# ZCD.net
KiCad netlist of a schematic drawn in Altium Designer
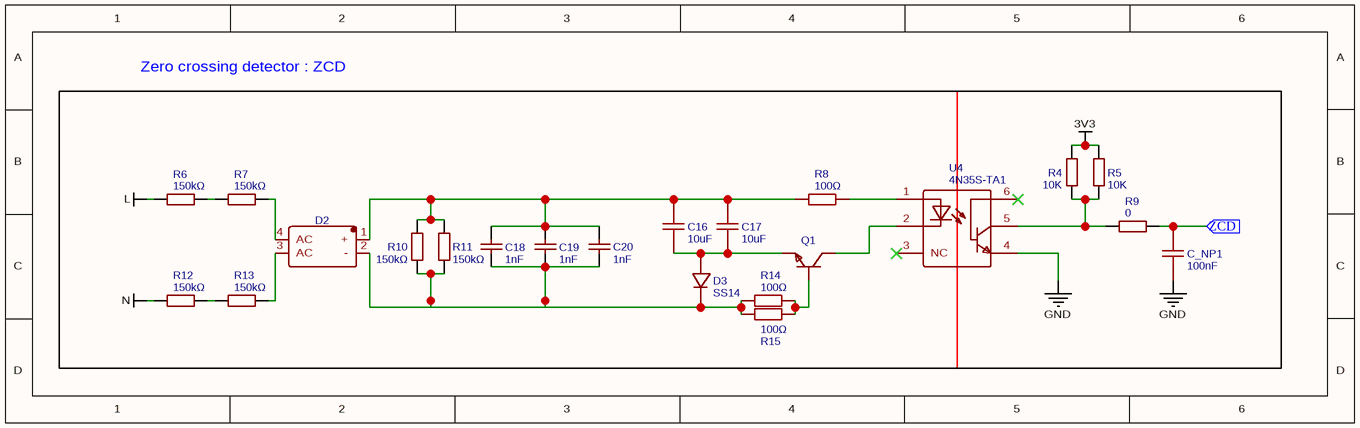
[diagram p0: ZCD.schdoc]

(export (version "E")
  (design (tool "Eeschema 10.0.6"))
  (components
    (comp (ref "C16")
      (value "10uF")
      (fields
        (field (name "BOM_MANUFACTURER PART") "0805F106M160NT")
        (field (name "BOM_SUPPLIER PART") "C90545")
      )
      (libsource (lib "altium-import") (part "root_1_10uF_"))
    )
    (comp (ref "C17")
      (value "10uF")
      (fields
        (field (name "BOM_MANUFACTURER PART") "0805F106M160NT")
        (field (name "BOM_SUPPLIER PART") "C90545")
      )
      (libsource (lib "altium-import") (part "root_1_10uF_"))
    )
    (comp (ref "C18")
      (value "1nF")
      (fields
        (field (name "BOM_MANUFACTURER PART") "CL10B102KB8NNNC")
        (field (name "BOM_SUPPLIER PART") "C1588")
      )
      (libsource (lib "altium-import") (part "root_1_1nF_"))
    )
    (comp (ref "C19")
      (value "1nF")
      (fields
        (field (name "BOM_MANUFACTURER PART") "CL10B102KB8NNNC")
        (field (name "BOM_SUPPLIER PART") "C1588")
      )
      (libsource (lib "altium-import") (part "root_1_1nF_"))
    )
    (comp (ref "C20")
      (value "1nF")
      (fields
        (field (name "BOM_MANUFACTURER PART") "CL10B102KB8NNNC")
        (field (name "BOM_SUPPLIER PART") "C1588")
      )
      (libsource (lib "altium-import") (part "root_1_1nF_"))
    )
    (comp (ref "C_NP1")
      (value "100nF")
      (fields
        (field (name "BOM_MANUFACTURER PART") "CL10B104KB8NNNC")
        (field (name "BOM_SUPPLIER PART") "C1591")
      )
      (libsource (lib "altium-import") (part "root_3_100nF_"))
    )
    (comp (ref "D2")
      (value "MB6S_C211754")
      (fields
        (field (name "BOM_SUPPLIER PART") "C211754")
        (field (name "BOM_MANUFACTURER PART") "MB6S")
        (field (name "CONTRIBUTOR") "LCSC")
      )
      (libsource (lib "altium-import") (part "root_0_MB6S_C211754_"))
    )
    (comp (ref "D3")
      (value "SS14")
      (fields (field (name "BOM_SUPPLIER PART") "C112424"))
      (libsource (lib "altium-import") (part "root_1_SS14_"))
    )
    (comp (ref "Q1")
      (value "MMBT2222A,215")
      (fields (field (name "BOM_SUPPLIER PART") "C179396") (field (name "CONTRIBUTOR") "LCSC"))
      (libsource (lib "altium-import") (part "root_1_MMBT2222A,215_"))
    )
    (comp (ref "R4")
      (value "10K")
      (fields
        (field (name "BOM_MANUFACTURER PART") "RC0603FR-0710KL")
        (field (name "BOM_SUPPLIER PART") "C98220")
      )
      (libsource (lib "altium-import") (part "root_1_10K_"))
    )
    (comp (ref "R5")
      (value "10K")
      (fields
        (field (name "BOM_MANUFACTURER PART") "RC0603FR-0710KL")
        (field (name "BOM_SUPPLIER PART") "C98220")
      )
      (libsource (lib "altium-import") (part "root_1_10K_"))
    )
    (comp (ref "R6")
      (value "150kΩ")
      (fields
        (field (name "BOM_MANUFACTURER PART") "1206W4F1503T5E")
        (field (name "BOM_SUPPLIER PART") "C17916")
      )
      (libsource (lib "altium-import") (part "root_0_150kΩ_"))
    )
    (comp (ref "R7")
      (value "150kΩ")
      (fields
        (field (name "BOM_MANUFACTURER PART") "1206W4F1503T5E")
        (field (name "BOM_SUPPLIER PART") "C17916")
      )
      (libsource (lib "altium-import") (part "root_0_150kΩ_"))
    )
    (comp (ref "R8")
      (value "100Ω")
      (fields
        (field (name "BOM_SUPPLIER PART") "C328334")
        (field (name "BOM_MANUFACTURER PART") "AECR0603F100RK9")
        (field (name "CONTRIBUTOR") "LCSC")
      )
      (libsource (lib "altium-import") (part "root_0_100Ω_"))
    )
    (comp (ref "R9")
      (value "0")
      (fields
        (field (name "BOM_MANUFACTURER PART") "RC0603JR-070RL")
        (field (name "BOM_SUPPLIER PART") "C95177")
      )
      (libsource (lib "altium-import") (part "root_0_0_"))
    )
    (comp (ref "R10")
      (value "150kΩ")
      (fields
        (field (name "BOM_MANUFACTURER PART") "1206W4F1503T5E")
        (field (name "BOM_SUPPLIER PART") "C17916")
      )
      (libsource (lib "altium-import") (part "root_1_150kΩ_"))
    )
    (comp (ref "R11")
      (value "150kΩ")
      (fields
        (field (name "BOM_MANUFACTURER PART") "1206W4F1503T5E")
        (field (name "BOM_SUPPLIER PART") "C17916")
      )
      (libsource (lib "altium-import") (part "root_1_150kΩ_"))
    )
    (comp (ref "R12")
      (value "150kΩ")
      (fields
        (field (name "BOM_MANUFACTURER PART") "1206W4F1503T5E")
        (field (name "BOM_SUPPLIER PART") "C17916")
      )
      (libsource (lib "altium-import") (part "root_0_150kΩ_"))
    )
    (comp (ref "R13")
      (value "150kΩ")
      (fields
        (field (name "BOM_MANUFACTURER PART") "1206W4F1503T5E")
        (field (name "BOM_SUPPLIER PART") "C17916")
      )
      (libsource (lib "altium-import") (part "root_0_150kΩ_"))
    )
    (comp (ref "R14")
      (value "100Ω")
      (fields
        (field (name "BOM_SUPPLIER PART") "C328334")
        (field (name "BOM_MANUFACTURER PART") "AECR0603F100RK9")
        (field (name "CONTRIBUTOR") "LCSC")
      )
      (libsource (lib "altium-import") (part "root_0_100Ω_"))
    )
    (comp (ref "R15")
      (value "100Ω")
      (fields
        (field (name "BOM_SUPPLIER PART") "C328334")
        (field (name "BOM_MANUFACTURER PART") "AECR0603F100RK9")
        (field (name "CONTRIBUTOR") "LCSC")
      )
      (libsource (lib "altium-import") (part "root_2_100Ω_"))
    )
    (comp (ref "U4")
      (value "4N35S-TA1")
      (fields (field (name "BOM_SUPPLIER PART") "C115444") (field (name "CONTRIBUTOR") "LCSC"))
      (libsource (lib "altium-import") (part "root_0_4N35S-TA1_"))
    )
  )
  (nets
    (net (code "1") (name "/ZCD") (class "Default")
      (node (ref "C_NP1") (pin "1") (pinfunction "1_1") (pintype "passive"))
      (node (ref "R9") (pin "2") (pinfunction "2_2") (pintype "passive"))
    )
    (net (code "2") (name "3V3") (class "Default")
      (node (ref "R4") (pin "2") (pinfunction "2_2") (pintype "passive"))
      (node (ref "R5") (pin "2") (pinfunction "2_2") (pintype "passive"))
    )
    (net (code "3") (name "GND") (class "Default")
      (node (ref "C_NP1") (pin "2") (pinfunction "2_2") (pintype "passive"))
      (node (ref "U4") (pin "4") (pinfunction "4_4") (pintype "passive"))
    )
    (net (code "4") (name "L") (class "Default")
      (node (ref "R6") (pin "1") (pinfunction "1_1") (pintype "passive"))
    )
    (net (code "5") (name "N") (class "Default")
      (node (ref "R12") (pin "1") (pinfunction "1_1") (pintype "passive"))
    )
    (net (code "6") (name "Net-(D2-+)") (class "Default")
      (node (ref "C16") (pin "2") (pinfunction "2_2") (pintype "passive"))
      (node (ref "C17") (pin "2") (pinfunction "2_2") (pintype "passive"))
      (node (ref "C18") (pin "2") (pinfunction "2_2") (pintype "passive"))
      (node (ref "C19") (pin "2") (pinfunction "2_2") (pintype "passive"))
      (node (ref "C20") (pin "2") (pinfunction "2_2") (pintype "passive"))
      (node (ref "D2") (pin "1") (pinfunction "+_1") (pintype "passive"))
      (node (ref "R10") (pin "2") (pinfunction "2_2") (pintype "passive"))
      (node (ref "R11") (pin "2") (pinfunction "2_2") (pintype "passive"))
      (node (ref "R8") (pin "1") (pinfunction "1_1") (pintype "passive"))
    )
    (net (code "7") (name "Net-(D2--)") (class "Default")
      (node (ref "C18") (pin "1") (pinfunction "1_1") (pintype "passive"))
      (node (ref "C19") (pin "1") (pinfunction "1_1") (pintype "passive"))
      (node (ref "C20") (pin "1") (pinfunction "1_1") (pintype "passive"))
      (node (ref "D2") (pin "2") (pinfunction "-_2") (pintype "passive"))
      (node (ref "D3") (pin "1") (pinfunction "C_1") (pintype "passive"))
      (node (ref "R10") (pin "1") (pinfunction "1_1") (pintype "passive"))
      (node (ref "R11") (pin "1") (pinfunction "1_1") (pintype "passive"))
      (node (ref "R14") (pin "1") (pinfunction "1_1") (pintype "passive"))
      (node (ref "R15") (pin "2") (pinfunction "2_2") (pintype "passive"))
    )
    (net (code "8") (name "Net-(D2-AC-Pad3)") (class "Default")
      (node (ref "D2") (pin "3") (pinfunction "AC_3") (pintype "passive"))
      (node (ref "R13") (pin "2") (pinfunction "2_2") (pintype "passive"))
    )
    (net (code "9") (name "Net-(D2-AC-Pad4)") (class "Default")
      (node (ref "D2") (pin "4") (pinfunction "AC_4") (pintype "passive"))
      (node (ref "R7") (pin "2") (pinfunction "2_2") (pintype "passive"))
    )
    (net (code "10") (name "Net-(D3-A)") (class "Default")
      (node (ref "C16") (pin "1") (pinfunction "1_1") (pintype "passive"))
      (node (ref "C17") (pin "1") (pinfunction "1_1") (pintype "passive"))
      (node (ref "D3") (pin "2") (pinfunction "A_2") (pintype "passive"))
      (node (ref "Q1") (pin "2") (pinfunction "E_2") (pintype "passive"))
    )
    (net (code "11") (name "Net-(Q1-B)") (class "Default")
      (node (ref "Q1") (pin "1") (pinfunction "B_1") (pintype "passive"))
      (node (ref "R14") (pin "2") (pinfunction "2_2") (pintype "passive"))
      (node (ref "R15") (pin "1") (pinfunction "1_1") (pintype "passive"))
    )
    (net (code "12") (name "Net-(Q1-C)") (class "Default")
      (node (ref "Q1") (pin "3") (pinfunction "C_3") (pintype "passive"))
      (node (ref "U4") (pin "2") (pinfunction "C_2") (pintype "passive"))
    )
    (net (code "13") (name "Net-(R4-Pad1)") (class "Default")
      (node (ref "R4") (pin "1") (pinfunction "1_1") (pintype "passive"))
      (node (ref "R5") (pin "1") (pinfunction "1_1") (pintype "passive"))
      (node (ref "R9") (pin "1") (pinfunction "1_1") (pintype "passive"))
      (node (ref "U4") (pin "5") (pinfunction "5_5") (pintype "passive"))
    )
    (net (code "14") (name "Net-(R6-Pad2)") (class "Default")
      (node (ref "R6") (pin "2") (pinfunction "2_2") (pintype "passive"))
      (node (ref "R7") (pin "1") (pinfunction "1_1") (pintype "passive"))
    )
    (net (code "15") (name "Net-(R12-Pad2)") (class "Default")
      (node (ref "R12") (pin "2") (pinfunction "2_2") (pintype "passive"))
      (node (ref "R13") (pin "1") (pinfunction "1_1") (pintype "passive"))
    )
    (net (code "16") (name "Net-(U4-AN)") (class "Default")
      (node (ref "R8") (pin "2") (pinfunction "2_2") (pintype "passive"))
      (node (ref "U4") (pin "1") (pinfunction "AN_1") (pintype "passive"))
    )
    (net (code "17") (name "unconnected-(U4-NC-Pad3)") (class "Default")
      (node (ref "U4") (pin "3") (pinfunction "NC_3") (pintype "passive+no_connect"))
    )
    (net (code "18") (name "unconnected-(U4-Pad6)") (class "Default")
      (node (ref "U4") (pin "6") (pinfunction "6_6") (pintype "passive+no_connect"))
    )
  )
)
